# NucleoBoard.net
KiCad netlist of a schematic drawn in Altium Designer
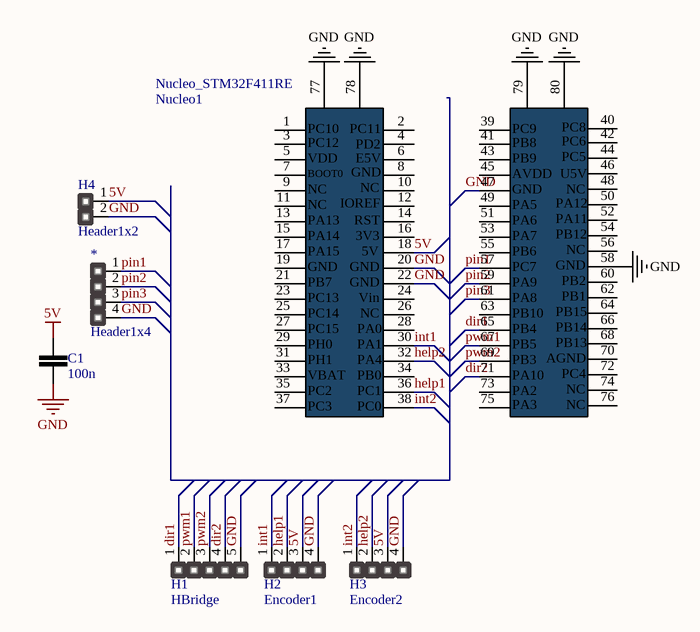
[diagram p0: NucleoBoard.SchDoc]

(export (version "E")
  (design (tool "Eeschema 10.0.6"))
  (components
    (comp (ref "*") (value "Header1x4") (footprint "Header1x4") (libsource (lib "") (part "Header1x4_1")))
    (comp (ref "C1") (value "100n") (footprint "C1(ceramic)") (libsource (lib "KILEX LIB SCH") (part "C1")))
    (comp (ref "H1")
      (value "HBridge")
      (footprint "Header1x5")
      (libsource (lib "KILEX LIB SCH") (part "Header1x5"))
    )
    (comp (ref "H2")
      (value "Encoder1")
      (footprint "Header1x4")
      (libsource (lib "KILEX LIB SCH") (part "Header1x4"))
    )
    (comp (ref "H3")
      (value "Encoder2")
      (footprint "Header1x4")
      (libsource (lib "KILEX LIB SCH") (part "Header1x4"))
    )
    (comp (ref "H4")
      (value "Header1x2")
      (footprint "Header1x2")
      (libsource (lib "KILEX LIB SCH") (part "Header1x2"))
    )
    (comp (ref "Nucleo1")
      (value "Nucleo_STM32F411RE")
      (footprint "Nucleo411")
      (libsource (lib "KILEX LIB SCH") (part "Nucleo_STM32F411RE"))
    )
  )
  (nets
    (net (code "1") (name "/dir1") (class "Default")
      (node (ref "H1") (pin "1") (pinfunction "1_1") (pintype "passive"))
      (node (ref "Nucleo1") (pin "65") (pinfunction "52_65") (pintype "passive"))
    )
    (net (code "2") (name "/dir2") (class "Default")
      (node (ref "H1") (pin "4") (pinfunction "4_4") (pintype "passive"))
      (node (ref "Nucleo1") (pin "71") (pinfunction "55_71") (pintype "passive"))
    )
    (net (code "3") (name "/help1") (class "Default")
      (node (ref "H2") (pin "2") (pinfunction "2_2") (pintype "passive"))
      (node (ref "Nucleo1") (pin "36") (pinfunction "19_36") (pintype "passive"))
    )
    (net (code "4") (name "/help2") (class "Default")
      (node (ref "H3") (pin "2") (pinfunction "2_2") (pintype "passive"))
      (node (ref "Nucleo1") (pin "32") (pinfunction "17_32") (pintype "passive"))
    )
    (net (code "5") (name "/int1") (class "Default")
      (node (ref "H2") (pin "1") (pinfunction "1_1") (pintype "passive"))
      (node (ref "Nucleo1") (pin "30") (pinfunction "16_30") (pintype "passive"))
    )
    (net (code "6") (name "/int2") (class "Default")
      (node (ref "H3") (pin "1") (pinfunction "1_1") (pintype "passive"))
      (node (ref "Nucleo1") (pin "38") (pinfunction "20_38") (pintype "passive"))
    )
    (net (code "7") (name "/pin1") (class "Default")
      (node (ref "*") (pin "1") (pinfunction "1_1") (pintype "passive"))
      (node (ref "Nucleo1") (pin "57") (pinfunction "48_57") (pintype "passive"))
    )
    (net (code "8") (name "/pin2") (class "Default")
      (node (ref "*") (pin "2") (pinfunction "2_2") (pintype "passive"))
      (node (ref "Nucleo1") (pin "59") (pinfunction "49_59") (pintype "passive"))
    )
    (net (code "9") (name "/pin3") (class "Default")
      (node (ref "*") (pin "3") (pinfunction "3_3") (pintype "passive"))
      (node (ref "Nucleo1") (pin "61") (pinfunction "50_61") (pintype "passive"))
    )
    (net (code "10") (name "/pwm1") (class "Default")
      (node (ref "H1") (pin "2") (pinfunction "2_2") (pintype "passive"))
      (node (ref "Nucleo1") (pin "67") (pinfunction "53_67") (pintype "passive"))
    )
    (net (code "11") (name "/pwm2") (class "Default")
      (node (ref "H1") (pin "3") (pinfunction "3_3") (pintype "passive"))
      (node (ref "Nucleo1") (pin "69") (pinfunction "54_69") (pintype "passive"))
    )
    (net (code "12") (name "5V") (class "Default")
      (node (ref "C1") (pin "1") (pinfunction "1_1") (pintype "passive"))
      (node (ref "H2") (pin "3") (pinfunction "3_3") (pintype "passive"))
      (node (ref "H3") (pin "3") (pinfunction "3_3") (pintype "passive"))
      (node (ref "H4") (pin "1") (pinfunction "1_1") (pintype "passive"))
      (node (ref "Nucleo1") (pin "18") (pinfunction "10_18") (pintype "passive"))
    )
    (net (code "13") (name "GND") (class "Default")
      (node (ref "*") (pin "4") (pinfunction "4_4") (pintype "passive"))
      (node (ref "C1") (pin "2") (pinfunction "2_2") (pintype "passive"))
      (node (ref "H1") (pin "5") (pinfunction "5_5") (pintype "passive"))
      (node (ref "H2") (pin "4") (pinfunction "4_4") (pintype "passive"))
      (node (ref "H3") (pin "4") (pinfunction "4_4") (pintype "passive"))
      (node (ref "H4") (pin "2") (pinfunction "2_2") (pintype "passive"))
      (node (ref "Nucleo1") (pin "20") (pinfunction "11_20") (pintype "passive"))
      (node (ref "Nucleo1") (pin "22") (pinfunction "12_22") (pintype "passive"))
      (node (ref "Nucleo1") (pin "47") (pinfunction "43_47") (pintype "passive"))
      (node (ref "Nucleo1") (pin "58") (pinfunction "49_58") (pintype "passive"))
      (node (ref "Nucleo1") (pin "77") (pinfunction "77_77") (pintype "passive"))
      (node (ref "Nucleo1") (pin "78") (pinfunction "78_78") (pintype "passive"))
      (node (ref "Nucleo1") (pin "79") (pinfunction "79_79") (pintype "passive"))
      (node (ref "Nucleo1") (pin "80") (pinfunction "80_80") (pintype "passive"))
    )
    (net (code "14") (name "unconnected-(Nucleo1-2-Pad3)") (class "Default")
      (node (ref "Nucleo1") (pin "3") (pinfunction "2_3") (pintype "passive"))
    )
    (net (code "15") (name "unconnected-(Nucleo1-3-Pad4)") (class "Default")
      (node (ref "Nucleo1") (pin "4") (pinfunction "3_4") (pintype "passive"))
    )
    (net (code "16") (name "unconnected-(Nucleo1-3-Pad5)") (class "Default")
      (node (ref "Nucleo1") (pin "5") (pinfunction "3_5") (pintype "passive"))
    )
    (net (code "17") (name "unconnected-(Nucleo1-4-Pad6)") (class "Default")
      (node (ref "Nucleo1") (pin "6") (pinfunction "4_6") (pintype "passive"))
    )
    (net (code "18") (name "unconnected-(Nucleo1-4-Pad7)") (class "Default")
      (node (ref "Nucleo1") (pin "7") (pinfunction "4_7") (pintype "passive"))
    )
    (net (code "19") (name "unconnected-(Nucleo1-5-Pad8)") (class "Default")
      (node (ref "Nucleo1") (pin "8") (pinfunction "5_8") (pintype "passive"))
    )
    (net (code "20") (name "unconnected-(Nucleo1-5-Pad9)") (class "Default")
      (node (ref "Nucleo1") (pin "9") (pinfunction "5_9") (pintype "passive"))
    )
    (net (code "21") (name "unconnected-(Nucleo1-6-Pad10)") (class "Default")
      (node (ref "Nucleo1") (pin "10") (pinfunction "6_10") (pintype "passive"))
    )
    (net (code "22") (name "unconnected-(Nucleo1-6-Pad11)") (class "Default")
      (node (ref "Nucleo1") (pin "11") (pinfunction "6_11") (pintype "passive"))
    )
    (net (code "23") (name "unconnected-(Nucleo1-7-Pad12)") (class "Default")
      (node (ref "Nucleo1") (pin "12") (pinfunction "7_12") (pintype "passive"))
    )
    (net (code "24") (name "unconnected-(Nucleo1-7-Pad13)") (class "Default")
      (node (ref "Nucleo1") (pin "13") (pinfunction "7_13") (pintype "passive"))
    )
    (net (code "25") (name "unconnected-(Nucleo1-8-Pad14)") (class "Default")
      (node (ref "Nucleo1") (pin "14") (pinfunction "8_14") (pintype "passive"))
    )
    (net (code "26") (name "unconnected-(Nucleo1-8-Pad15)") (class "Default")
      (node (ref "Nucleo1") (pin "15") (pinfunction "8_15") (pintype "passive"))
    )
    (net (code "27") (name "unconnected-(Nucleo1-9-Pad16)") (class "Default")
      (node (ref "Nucleo1") (pin "16") (pinfunction "9_16") (pintype "passive"))
    )
    (net (code "28") (name "unconnected-(Nucleo1-9-Pad17)") (class "Default")
      (node (ref "Nucleo1") (pin "17") (pinfunction "9_17") (pintype "passive"))
    )
    (net (code "29") (name "unconnected-(Nucleo1-10-Pad19)") (class "Default")
      (node (ref "Nucleo1") (pin "19") (pinfunction "10_19") (pintype "passive"))
    )
    (net (code "30") (name "unconnected-(Nucleo1-11-Pad21)") (class "Default")
      (node (ref "Nucleo1") (pin "21") (pinfunction "11_21") (pintype "passive"))
    )
    (net (code "31") (name "unconnected-(Nucleo1-12-Pad23)") (class "Default")
      (node (ref "Nucleo1") (pin "23") (pinfunction "12_23") (pintype "passive"))
    )
    (net (code "32") (name "unconnected-(Nucleo1-13-Pad24)") (class "Default")
      (node (ref "Nucleo1") (pin "24") (pinfunction "13_24") (pintype "passive"))
    )
    (net (code "33") (name "unconnected-(Nucleo1-13-Pad25)") (class "Default")
      (node (ref "Nucleo1") (pin "25") (pinfunction "13_25") (pintype "passive"))
    )
    (net (code "34") (name "unconnected-(Nucleo1-14-Pad26)") (class "Default")
      (node (ref "Nucleo1") (pin "26") (pinfunction "14_26") (pintype "passive"))
    )
    (net (code "35") (name "unconnected-(Nucleo1-14-Pad27)") (class "Default")
      (node (ref "Nucleo1") (pin "27") (pinfunction "14_27") (pintype "passive"))
    )
    (net (code "36") (name "unconnected-(Nucleo1-15-Pad28)") (class "Default")
      (node (ref "Nucleo1") (pin "28") (pinfunction "15_28") (pintype "passive"))
    )
    (net (code "37") (name "unconnected-(Nucleo1-15-Pad29)") (class "Default")
      (node (ref "Nucleo1") (pin "29") (pinfunction "15_29") (pintype "passive"))
    )
    (net (code "38") (name "unconnected-(Nucleo1-16-Pad31)") (class "Default")
      (node (ref "Nucleo1") (pin "31") (pinfunction "16_31") (pintype "passive"))
    )
    (net (code "39") (name "unconnected-(Nucleo1-17-Pad33)") (class "Default")
      (node (ref "Nucleo1") (pin "33") (pinfunction "17_33") (pintype "passive"))
    )
    (net (code "40") (name "unconnected-(Nucleo1-18-Pad34)") (class "Default")
      (node (ref "Nucleo1") (pin "34") (pinfunction "18_34") (pintype "passive"))
    )
    (net (code "41") (name "unconnected-(Nucleo1-18-Pad35)") (class "Default")
      (node (ref "Nucleo1") (pin "35") (pinfunction "18_35") (pintype "passive"))
    )
    (net (code "42") (name "unconnected-(Nucleo1-19-Pad37)") (class "Default")
      (node (ref "Nucleo1") (pin "37") (pinfunction "19_37") (pintype "passive"))
    )
    (net (code "43") (name "unconnected-(Nucleo1-40-Pad41)") (class "Default")
      (node (ref "Nucleo1") (pin "41") (pinfunction "40_41") (pintype "passive"))
    )
    (net (code "44") (name "unconnected-(Nucleo1-41-Pad42)") (class "Default")
      (node (ref "Nucleo1") (pin "42") (pinfunction "41_42") (pintype "passive"))
    )
    (net (code "45") (name "unconnected-(Nucleo1-41-Pad43)") (class "Default")
      (node (ref "Nucleo1") (pin "43") (pinfunction "41_43") (pintype "passive"))
    )
    (net (code "46") (name "unconnected-(Nucleo1-42-Pad44)") (class "Default")
      (node (ref "Nucleo1") (pin "44") (pinfunction "42_44") (pintype "passive"))
    )
    (net (code "47") (name "unconnected-(Nucleo1-42-Pad45)") (class "Default")
      (node (ref "Nucleo1") (pin "45") (pinfunction "42_45") (pintype "passive"))
    )
    (net (code "48") (name "unconnected-(Nucleo1-43-Pad46)") (class "Default")
      (node (ref "Nucleo1") (pin "46") (pinfunction "43_46") (pintype "passive"))
    )
    (net (code "49") (name "unconnected-(Nucleo1-44-Pad48)") (class "Default")
      (node (ref "Nucleo1") (pin "48") (pinfunction "44_48") (pintype "passive"))
    )
    (net (code "50") (name "unconnected-(Nucleo1-44-Pad49)") (class "Default")
      (node (ref "Nucleo1") (pin "49") (pinfunction "44_49") (pintype "passive"))
    )
    (net (code "51") (name "unconnected-(Nucleo1-45-Pad50)") (class "Default")
      (node (ref "Nucleo1") (pin "50") (pinfunction "45_50") (pintype "passive"))
    )
    (net (code "52") (name "unconnected-(Nucleo1-45-Pad51)") (class "Default")
      (node (ref "Nucleo1") (pin "51") (pinfunction "45_51") (pintype "passive"))
    )
    (net (code "53") (name "unconnected-(Nucleo1-46-Pad52)") (class "Default")
      (node (ref "Nucleo1") (pin "52") (pinfunction "46_52") (pintype "passive"))
    )
    (net (code "54") (name "unconnected-(Nucleo1-46-Pad53)") (class "Default")
      (node (ref "Nucleo1") (pin "53") (pinfunction "46_53") (pintype "passive"))
    )
    (net (code "55") (name "unconnected-(Nucleo1-47-Pad54)") (class "Default")
      (node (ref "Nucleo1") (pin "54") (pinfunction "47_54") (pintype "passive"))
    )
    (net (code "56") (name "unconnected-(Nucleo1-47-Pad55)") (class "Default")
      (node (ref "Nucleo1") (pin "55") (pinfunction "47_55") (pintype "passive"))
    )
    (net (code "57") (name "unconnected-(Nucleo1-48-Pad56)") (class "Default")
      (node (ref "Nucleo1") (pin "56") (pinfunction "48_56") (pintype "passive"))
    )
    (net (code "58") (name "unconnected-(Nucleo1-50-Pad60)") (class "Default")
      (node (ref "Nucleo1") (pin "60") (pinfunction "50_60") (pintype "passive"))
    )
    (net (code "59") (name "unconnected-(Nucleo1-51-Pad62)") (class "Default")
      (node (ref "Nucleo1") (pin "62") (pinfunction "51_62") (pintype "passive"))
    )
    (net (code "60") (name "unconnected-(Nucleo1-51-Pad63)") (class "Default")
      (node (ref "Nucleo1") (pin "63") (pinfunction "51_63") (pintype "passive"))
    )
    (net (code "61") (name "unconnected-(Nucleo1-52-Pad64)") (class "Default")
      (node (ref "Nucleo1") (pin "64") (pinfunction "52_64") (pintype "passive"))
    )
    (net (code "62") (name "unconnected-(Nucleo1-53-Pad66)") (class "Default")
      (node (ref "Nucleo1") (pin "66") (pinfunction "53_66") (pintype "passive"))
    )
    (net (code "63") (name "unconnected-(Nucleo1-54-Pad68)") (class "Default")
      (node (ref "Nucleo1") (pin "68") (pinfunction "54_68") (pintype "passive"))
    )
    (net (code "64") (name "unconnected-(Nucleo1-55-Pad70)") (class "Default")
      (node (ref "Nucleo1") (pin "70") (pinfunction "55_70") (pintype "passive"))
    )
    (net (code "65") (name "unconnected-(Nucleo1-56-Pad72)") (class "Default")
      (node (ref "Nucleo1") (pin "72") (pinfunction "56_72") (pintype "passive"))
    )
    (net (code "66") (name "unconnected-(Nucleo1-56-Pad73)") (class "Default")
      (node (ref "Nucleo1") (pin "73") (pinfunction "56_73") (pintype "passive"))
    )
    (net (code "67") (name "unconnected-(Nucleo1-57-Pad74)") (class "Default")
      (node (ref "Nucleo1") (pin "74") (pinfunction "57_74") (pintype "passive"))
    )
    (net (code "68") (name "unconnected-(Nucleo1-57-Pad75)") (class "Default")
      (node (ref "Nucleo1") (pin "75") (pinfunction "57_75") (pintype "passive"))
    )
    (net (code "69") (name "unconnected-(Nucleo1-58-Pad76)") (class "Default")
      (node (ref "Nucleo1") (pin "76") (pinfunction "58_76") (pintype "passive"))
    )
    (net (code "70") (name "unconnected-(Nucleo1-Pad1)") (class "Default")
      (node (ref "Nucleo1") (pin "1") (pinfunction "1_1") (pintype "passive"))
    )
    (net (code "71") (name "unconnected-(Nucleo1-Pad2)") (class "Default")
      (node (ref "Nucleo1") (pin "2") (pinfunction "2_2") (pintype "passive"))
    )
    (net (code "72") (name "unconnected-(Nucleo1-Pad39)") (class "Default")
      (node (ref "Nucleo1") (pin "39") (pinfunction "39_39") (pintype "passive"))
    )
    (net (code "73") (name "unconnected-(Nucleo1-Pad40)") (class "Default")
      (node (ref "Nucleo1") (pin "40") (pinfunction "40_40") (pintype "passive"))
    )
  )
)
